# Sheet1.net
KiCad netlist of a schematic drawn in Altium Designer
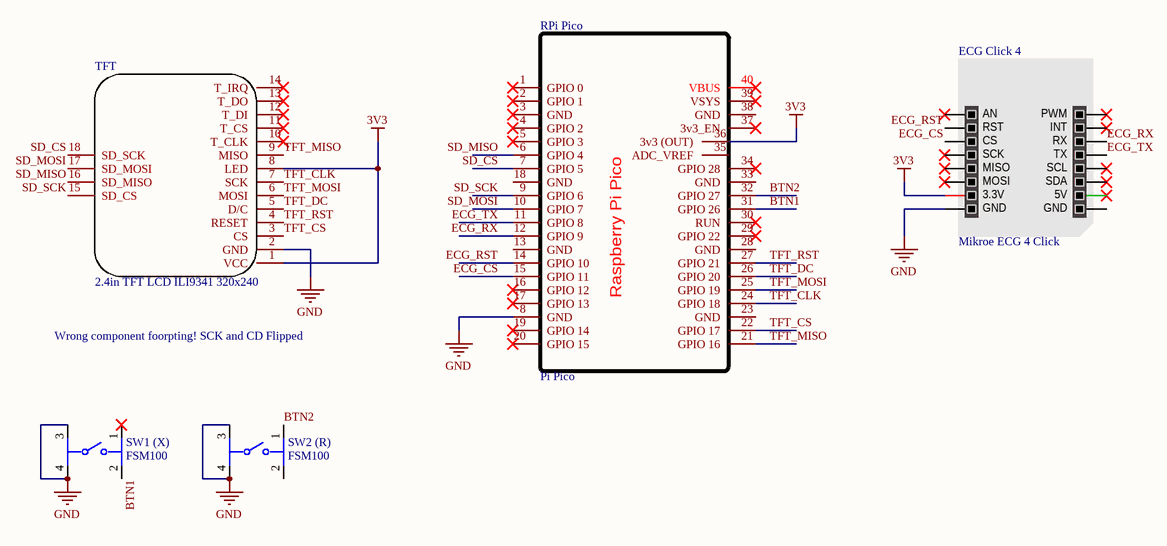
[diagram p0: Sheet1.SchDoc]

(export (version "E")
  (design (tool "Eeschema 10.0.6"))
  (components
    (comp (ref "ECG Click 4")
      (value "Mikroe ECG 4 Click")
      (footprint "Mikroe ECG 4 Click-Footprint-1")
      (libsource (lib "BINIT PODDAR") (part "Mikroe ECG 4 Click-Symbol-1"))
    )
    (comp (ref "RPi Pico")
      (value "Pi Pico")
      (footprint "Pi Pico-Footprint-1")
      (libsource (lib "BINIT PODDAR") (part "Pi Pico-Symbol-1"))
    )
    (comp (ref "SW1 (X)")
      (value "FSM100")
      (footprint "FP-FSM100-MFG")
      (description "SWITCH TACTILE SPST-NO 0.05A 24V")
      (libsource (lib "Altium Content Vault") (part "1adf0dd01260c80cf25a44bfd6b99ba"))
    )
    (comp (ref "SW2 (R)")
      (value "FSM100")
      (footprint "FP-FSM100-MFG")
      (description "SWITCH TACTILE SPST-NO 0.05A 24V")
      (libsource (lib "Altium Content Vault") (part "1adf0dd01260c80cf25a44bfd6b99ba"))
    )
    (comp (ref "TFT")
      (value "2.4in TFT LCD ILI9341 320x240")
      (footprint "2.4in TFT LCD ILI9341 320x240-Footprint-1")
      (libsource (lib "BINIT PODDAR") (part "2.4in TFT LCD ILI9341 320x240-Symbol-1"))
    )
  )
  (nets
    (net (code "1") (name "/BTN1") (class "Default")
      (node (ref "RPi Pico") (pin "31") (pinfunction "GPIO_26_31") (pintype "passive"))
      (node (ref "SW1 (X)") (pin "2") (pinfunction "2_2") (pintype "passive"))
    )
    (net (code "2") (name "/BTN2") (class "Default")
      (node (ref "RPi Pico") (pin "32") (pinfunction "GPIO_27_32") (pintype "passive"))
      (node (ref "SW2 (R)") (pin "1") (pinfunction "1_1") (pintype "passive"))
    )
    (net (code "3") (name "/ECG_CS") (class "Default")
      (node (ref "ECG Click 4") (pin "3") (pinfunction "CS_3") (pintype "passive"))
      (node (ref "RPi Pico") (pin "15") (pinfunction "GPIO_11_15") (pintype "passive"))
    )
    (net (code "4") (name "/ECG_RST") (class "Default")
      (node (ref "ECG Click 4") (pin "2") (pinfunction "RST_2") (pintype "passive"))
      (node (ref "RPi Pico") (pin "14") (pinfunction "GPIO_10_14") (pintype "passive"))
    )
    (net (code "5") (name "/ECG_RX") (class "Default")
      (node (ref "ECG Click 4") (pin "14") (pinfunction "RX_14") (pintype "passive"))
      (node (ref "RPi Pico") (pin "12") (pinfunction "GPIO_9_12") (pintype "passive"))
    )
    (net (code "6") (name "/ECG_TX") (class "Default")
      (node (ref "ECG Click 4") (pin "13") (pinfunction "TX_13") (pintype "passive"))
      (node (ref "RPi Pico") (pin "11") (pinfunction "GPIO_8_11") (pintype "passive"))
    )
    (net (code "7") (name "/SD_CS") (class "Default")
      (node (ref "RPi Pico") (pin "7") (pinfunction "GPIO_5_7") (pintype "passive"))
      (node (ref "TFT") (pin "18") (pinfunction "SD_SCK_18") (pintype "passive"))
    )
    (net (code "8") (name "/SD_MISO") (class "Default")
      (node (ref "RPi Pico") (pin "6") (pinfunction "GPIO_4_6") (pintype "passive"))
      (node (ref "TFT") (pin "16") (pinfunction "SD_MISO_16") (pintype "passive"))
    )
    (net (code "9") (name "/SD_MOSI") (class "Default")
      (node (ref "RPi Pico") (pin "10") (pinfunction "GPIO_7_10") (pintype "passive"))
      (node (ref "TFT") (pin "17") (pinfunction "SD_MOSI_17") (pintype "passive"))
    )
    (net (code "10") (name "/SD_SCK") (class "Default")
      (node (ref "RPi Pico") (pin "9") (pinfunction "GPIO_6_9") (pintype "passive"))
      (node (ref "TFT") (pin "15") (pinfunction "SD_CS_15") (pintype "passive"))
    )
    (net (code "11") (name "/TFT_CLK") (class "Default")
      (node (ref "RPi Pico") (pin "24") (pinfunction "GPIO_18_24") (pintype "passive"))
      (node (ref "TFT") (pin "7") (pinfunction "SCK_7") (pintype "passive"))
    )
    (net (code "12") (name "/TFT_CS") (class "Default")
      (node (ref "RPi Pico") (pin "22") (pinfunction "GPIO_17_22") (pintype "passive"))
      (node (ref "TFT") (pin "3") (pinfunction "CS_3") (pintype "passive"))
    )
    (net (code "13") (name "/TFT_DC") (class "Default")
      (node (ref "RPi Pico") (pin "26") (pinfunction "GPIO_20_26") (pintype "passive"))
      (node (ref "TFT") (pin "5") (pinfunction "D/C_5") (pintype "passive"))
    )
    (net (code "14") (name "/TFT_MISO") (class "Default")
      (node (ref "RPi Pico") (pin "21") (pinfunction "GPIO_16_21") (pintype "passive"))
      (node (ref "TFT") (pin "9") (pinfunction "MISO_9") (pintype "passive"))
    )
    (net (code "15") (name "/TFT_MOSI") (class "Default")
      (node (ref "RPi Pico") (pin "25") (pinfunction "GPIO_19_25") (pintype "passive"))
      (node (ref "TFT") (pin "6") (pinfunction "MOSI_6") (pintype "passive"))
    )
    (net (code "16") (name "/TFT_RST") (class "Default")
      (node (ref "RPi Pico") (pin "27") (pinfunction "GPIO_21_27") (pintype "passive"))
      (node (ref "TFT") (pin "4") (pinfunction "RESET_4") (pintype "passive"))
    )
    (net (code "17") (name "3V3") (class "Default")
      (node (ref "ECG Click 4") (pin "7") (pinfunction "3.3V_7") (pintype "passive"))
      (node (ref "RPi Pico") (pin "36") (pinfunction "3v3_(OUT)_36") (pintype "passive"))
      (node (ref "TFT") (pin "1") (pinfunction "VCC_1") (pintype "passive"))
      (node (ref "TFT") (pin "8") (pinfunction "LED_8") (pintype "passive"))
    )
    (net (code "18") (name "GND") (class "Default")
      (node (ref "ECG Click 4") (pin "8") (pinfunction "GND_8") (pintype "passive"))
      (node (ref "RPi Pico") (pin "8") (pinfunction "GND_8") (pintype "passive"))
      (node (ref "SW1 (X)") (pin "3") (pinfunction "3_3") (pintype "passive"))
      (node (ref "SW1 (X)") (pin "4") (pinfunction "4_4") (pintype "passive"))
      (node (ref "SW2 (R)") (pin "3") (pinfunction "3_3") (pintype "passive"))
      (node (ref "SW2 (R)") (pin "4") (pinfunction "4_4") (pintype "passive"))
      (node (ref "TFT") (pin "2") (pinfunction "GND_2") (pintype "passive"))
    )
    (net (code "19") (name "unconnected-(ECG Click 4-5V-Pad10)") (class "Default")
      (node (ref "ECG Click 4") (pin "10") (pinfunction "5V_10") (pintype "passive+no_connect"))
    )
    (net (code "20") (name "unconnected-(ECG Click 4-AN-Pad1)") (class "Default")
      (node (ref "ECG Click 4") (pin "1") (pinfunction "AN_1") (pintype "passive+no_connect"))
    )
    (net (code "21") (name "unconnected-(ECG Click 4-GND-Pad9)") (class "Default")
      (node (ref "ECG Click 4") (pin "9") (pinfunction "GND_9") (pintype "passive"))
    )
    (net (code "22") (name "unconnected-(ECG Click 4-INT-Pad15)") (class "Default")
      (node (ref "ECG Click 4") (pin "15") (pinfunction "INT_15") (pintype "passive+no_connect"))
    )
    (net (code "23") (name "unconnected-(ECG Click 4-MISO-Pad5)") (class "Default")
      (node (ref "ECG Click 4") (pin "5") (pinfunction "MISO_5") (pintype "passive+no_connect"))
    )
    (net (code "24") (name "unconnected-(ECG Click 4-MOSI-Pad6)") (class "Default")
      (node (ref "ECG Click 4") (pin "6") (pinfunction "MOSI_6") (pintype "passive+no_connect"))
    )
    (net (code "25") (name "unconnected-(ECG Click 4-PWM-Pad16)") (class "Default")
      (node (ref "ECG Click 4") (pin "16") (pinfunction "PWM_16") (pintype "passive+no_connect"))
    )
    (net (code "26") (name "unconnected-(ECG Click 4-SCK-Pad4)") (class "Default")
      (node (ref "ECG Click 4") (pin "4") (pinfunction "SCK_4") (pintype "passive+no_connect"))
    )
    (net (code "27") (name "unconnected-(ECG Click 4-SCL-Pad12)") (class "Default")
      (node (ref "ECG Click 4") (pin "12") (pinfunction "SCL_12") (pintype "passive+no_connect"))
    )
    (net (code "28") (name "unconnected-(ECG Click 4-SDA-Pad11)") (class "Default")
      (node (ref "ECG Click 4") (pin "11") (pinfunction "SDA_11") (pintype "passive+no_connect"))
    )
    (net (code "29") (name "unconnected-(RPi Pico-3v3_EN-Pad37)") (class "Default")
      (node (ref "RPi Pico") (pin "37") (pinfunction "3v3_EN_37") (pintype "passive+no_connect"))
    )
    (net (code "30") (name "unconnected-(RPi Pico-ADC_VREF-Pad35)") (class "Default")
      (node (ref "RPi Pico") (pin "35") (pinfunction "ADC_VREF_35") (pintype "passive"))
    )
    (net (code "31") (name "unconnected-(RPi Pico-GND-Pad3)") (class "Default")
      (node (ref "RPi Pico") (pin "3") (pinfunction "GND_3") (pintype "passive+no_connect"))
    )
    (net (code "32") (name "unconnected-(RPi Pico-GND-Pad13)") (class "Default")
      (node (ref "RPi Pico") (pin "13") (pinfunction "GND_13") (pintype "passive"))
    )
    (net (code "33") (name "unconnected-(RPi Pico-GND-Pad18)") (class "Default")
      (node (ref "RPi Pico") (pin "18") (pinfunction "GND_18") (pintype "passive"))
    )
    (net (code "34") (name "unconnected-(RPi Pico-GND-Pad23)") (class "Default")
      (node (ref "RPi Pico") (pin "23") (pinfunction "GND_23") (pintype "passive"))
    )
    (net (code "35") (name "unconnected-(RPi Pico-GND-Pad28)") (class "Default")
      (node (ref "RPi Pico") (pin "28") (pinfunction "GND_28") (pintype "passive"))
    )
    (net (code "36") (name "unconnected-(RPi Pico-GND-Pad33)") (class "Default")
      (node (ref "RPi Pico") (pin "33") (pinfunction "GND_33") (pintype "passive"))
    )
    (net (code "37") (name "unconnected-(RPi Pico-GND-Pad38)") (class "Default")
      (node (ref "RPi Pico") (pin "38") (pinfunction "GND_38") (pintype "passive"))
    )
    (net (code "38") (name "unconnected-(RPi Pico-GPIO_0-Pad1)") (class "Default")
      (node (ref "RPi Pico") (pin "1") (pinfunction "GPIO_0_1") (pintype "passive+no_connect"))
    )
    (net (code "39") (name "unconnected-(RPi Pico-GPIO_1-Pad2)") (class "Default")
      (node (ref "RPi Pico") (pin "2") (pinfunction "GPIO_1_2") (pintype "passive+no_connect"))
    )
    (net (code "40") (name "unconnected-(RPi Pico-GPIO_2-Pad4)") (class "Default")
      (node (ref "RPi Pico") (pin "4") (pinfunction "GPIO_2_4") (pintype "passive+no_connect"))
    )
    (net (code "41") (name "unconnected-(RPi Pico-GPIO_3-Pad5)") (class "Default")
      (node (ref "RPi Pico") (pin "5") (pinfunction "GPIO_3_5") (pintype "passive+no_connect"))
    )
    (net (code "42") (name "unconnected-(RPi Pico-GPIO_12-Pad16)") (class "Default")
      (node (ref "RPi Pico") (pin "16") (pinfunction "GPIO_12_16") (pintype "passive+no_connect"))
    )
    (net (code "43") (name "unconnected-(RPi Pico-GPIO_13-Pad17)") (class "Default")
      (node (ref "RPi Pico") (pin "17") (pinfunction "GPIO_13_17") (pintype "passive+no_connect"))
    )
    (net (code "44") (name "unconnected-(RPi Pico-GPIO_14-Pad19)") (class "Default")
      (node (ref "RPi Pico") (pin "19") (pinfunction "GPIO_14_19") (pintype "passive+no_connect"))
    )
    (net (code "45") (name "unconnected-(RPi Pico-GPIO_15-Pad20)") (class "Default")
      (node (ref "RPi Pico") (pin "20") (pinfunction "GPIO_15_20") (pintype "passive+no_connect"))
    )
    (net (code "46") (name "unconnected-(RPi Pico-GPIO_22-Pad29)") (class "Default")
      (node (ref "RPi Pico") (pin "29") (pinfunction "GPIO_22_29") (pintype "passive+no_connect"))
    )
    (net (code "47") (name "unconnected-(RPi Pico-GPIO_28-Pad34)") (class "Default")
      (node (ref "RPi Pico") (pin "34") (pinfunction "GPIO_28_34") (pintype "passive+no_connect"))
    )
    (net (code "48") (name "unconnected-(RPi Pico-RUN-Pad30)") (class "Default")
      (node (ref "RPi Pico") (pin "30") (pinfunction "RUN_30") (pintype "passive+no_connect"))
    )
    (net (code "49") (name "unconnected-(RPi Pico-VBUS-Pad40)") (class "Default")
      (node (ref "RPi Pico") (pin "40") (pinfunction "VBUS_40") (pintype "passive+no_connect"))
    )
    (net (code "50") (name "unconnected-(RPi Pico-VSYS-Pad39)") (class "Default")
      (node (ref "RPi Pico") (pin "39") (pinfunction "VSYS_39") (pintype "passive+no_connect"))
    )
    (net (code "51") (name "unconnected-(SW1 (X)-Pad1)") (class "Default")
      (node (ref "SW1 (X)") (pin "1") (pinfunction "1_1") (pintype "passive+no_connect"))
    )
    (net (code "52") (name "unconnected-(SW2 (R)-Pad2)") (class "Default")
      (node (ref "SW2 (R)") (pin "2") (pinfunction "2_2") (pintype "passive"))
    )
    (net (code "53") (name "unconnected-(TFT-T_CLK-Pad10)") (class "Default")
      (node (ref "TFT") (pin "10") (pinfunction "T_CLK_10") (pintype "passive+no_connect"))
    )
    (net (code "54") (name "unconnected-(TFT-T_CS-Pad11)") (class "Default")
      (node (ref "TFT") (pin "11") (pinfunction "T_CS_11") (pintype "passive+no_connect"))
    )
    (net (code "55") (name "unconnected-(TFT-T_DI-Pad12)") (class "Default")
      (node (ref "TFT") (pin "12") (pinfunction "T_DI_12") (pintype "passive+no_connect"))
    )
    (net (code "56") (name "unconnected-(TFT-T_DO-Pad13)") (class "Default")
      (node (ref "TFT") (pin "13") (pinfunction "T_DO_13") (pintype "passive+no_connect"))
    )
    (net (code "57") (name "unconnected-(TFT-T_IRQ-Pad14)") (class "Default")
      (node (ref "TFT") (pin "14") (pinfunction "T_IRQ_14") (pintype "passive+no_connect"))
    )
  )
)
